# VNH2SP30_dual.net
KiCad netlist of a schematic drawn in EAGLE
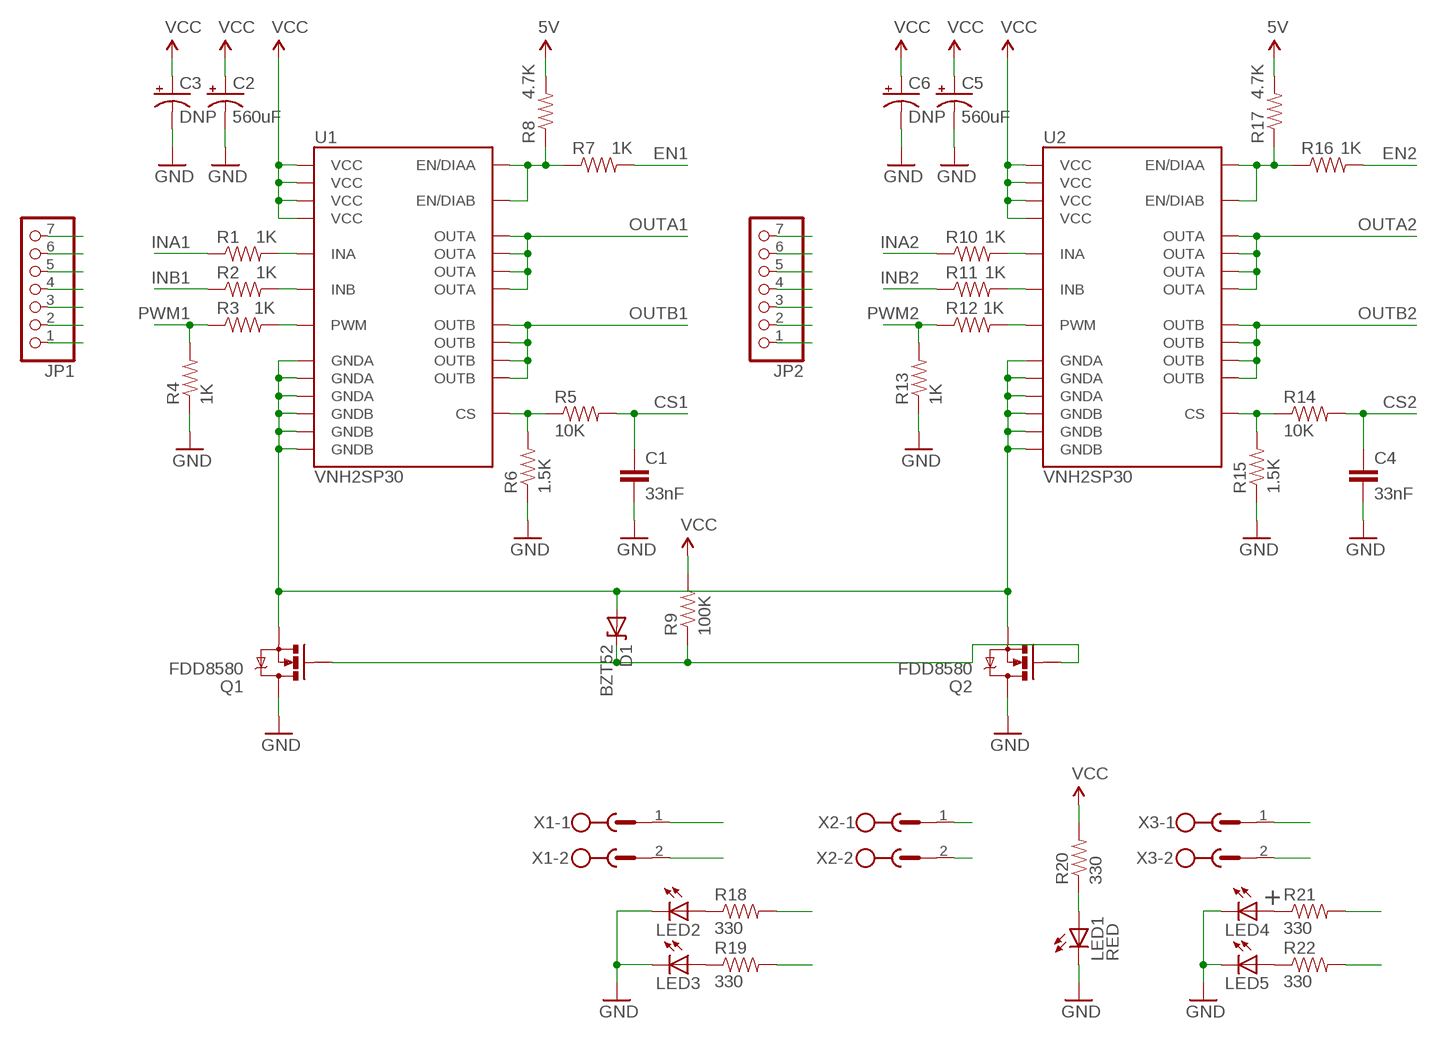
[diagram p0: schematic, sheet 1]

(export (version "E")
  (design (tool "Eeschema 10.0.6"))
  (components
    (comp (ref "C1")
      (value "33nF")
      (footprint "eagle-import:1206")
      (libsource (lib "eagle-import") (part "CAP1206"))
    )
    (comp (ref "C2")
      (value "560uF")
      (footprint "eagle-import:PANASONIC_G")
      (libsource (lib "eagle-import") (part "CAP_POLG"))
    )
    (comp (ref "C3")
      (value "DNP")
      (footprint "eagle-import:CPOL-RADIAL-1000UF-25V")
      (libsource (lib "eagle-import") (part "CAP_POLPTH4"))
    )
    (comp (ref "C4")
      (value "33nF")
      (footprint "eagle-import:1206")
      (libsource (lib "eagle-import") (part "CAP1206"))
    )
    (comp (ref "C5")
      (value "560uF")
      (footprint "eagle-import:PANASONIC_G")
      (libsource (lib "eagle-import") (part "CAP_POLG"))
    )
    (comp (ref "C6")
      (value "DNP")
      (footprint "eagle-import:CPOL-RADIAL-1000UF-25V")
      (libsource (lib "eagle-import") (part "CAP_POLPTH4"))
    )
    (comp (ref "D1")
      (value "BZT52")
      (footprint "eagle-import:SMB-DIODE")
      (libsource (lib "eagle-import") (part "DIODE-ZENERSMB"))
    )
    (comp (ref "JP1")
      (value "PINHD-1X7")
      (footprint "eagle-import:1X07")
      (libsource (lib "eagle-import") (part "PINHD-1X7"))
    )
    (comp (ref "JP2")
      (value "PINHD-1X7")
      (footprint "eagle-import:1X07")
      (libsource (lib "eagle-import") (part "PINHD-1X7"))
    )
    (comp (ref "LED1")
      (value "RED")
      (footprint "eagle-import:CHIPLED_1206")
      (libsource (lib "eagle-import") (part "LEDCHIPLED_1206"))
    )
    (comp (ref "LED2")
      (value "GREEN")
      (footprint "eagle-import:CHIPLED_1206")
      (libsource (lib "eagle-import") (part "LEDCHIPLED_1206"))
    )
    (comp (ref "LED3")
      (value "GREEN")
      (footprint "eagle-import:CHIPLED_1206")
      (libsource (lib "eagle-import") (part "LEDCHIPLED_1206"))
    )
    (comp (ref "LED4")
      (value "GREEN")
      (footprint "eagle-import:CHIPLED_1206")
      (libsource (lib "eagle-import") (part "LEDCHIPLED_1206"))
    )
    (comp (ref "LED5")
      (value "GREEN")
      (footprint "eagle-import:CHIPLED_1206")
      (libsource (lib "eagle-import") (part "LEDCHIPLED_1206"))
    )
    (comp (ref "Q1")
      (value "FDD8580")
      (footprint "eagle-import:DPAK")
      (libsource (lib "eagle-import") (part "MOSFET-NCHANNELFDD8580"))
    )
    (comp (ref "Q2")
      (value "FDD8580")
      (footprint "eagle-import:DPAK")
      (libsource (lib "eagle-import") (part "MOSFET-NCHANNELFDD8580"))
    )
    (comp (ref "R1")
      (value "1K")
      (footprint "eagle-import:1206")
      (libsource (lib "eagle-import") (part "RESISTOR1206"))
    )
    (comp (ref "R2")
      (value "1K")
      (footprint "eagle-import:1206")
      (libsource (lib "eagle-import") (part "RESISTOR1206"))
    )
    (comp (ref "R3")
      (value "1K")
      (footprint "eagle-import:1206")
      (libsource (lib "eagle-import") (part "RESISTOR1206"))
    )
    (comp (ref "R4")
      (value "1K")
      (footprint "eagle-import:1206")
      (libsource (lib "eagle-import") (part "RESISTOR1206"))
    )
    (comp (ref "R5")
      (value "10K")
      (footprint "eagle-import:1206")
      (libsource (lib "eagle-import") (part "RESISTOR1206"))
    )
    (comp (ref "R6")
      (value "1.5K")
      (footprint "eagle-import:1206")
      (libsource (lib "eagle-import") (part "RESISTOR1206"))
    )
    (comp (ref "R7")
      (value "1K")
      (footprint "eagle-import:1206")
      (libsource (lib "eagle-import") (part "RESISTOR1206"))
    )
    (comp (ref "R8")
      (value "4.7K")
      (footprint "eagle-import:1206")
      (libsource (lib "eagle-import") (part "RESISTOR1206"))
    )
    (comp (ref "R9")
      (value "100K")
      (footprint "eagle-import:1206")
      (libsource (lib "eagle-import") (part "RESISTOR1206"))
    )
    (comp (ref "R10")
      (value "1K")
      (footprint "eagle-import:1206")
      (libsource (lib "eagle-import") (part "RESISTOR1206"))
    )
    (comp (ref "R11")
      (value "1K")
      (footprint "eagle-import:1206")
      (libsource (lib "eagle-import") (part "RESISTOR1206"))
    )
    (comp (ref "R12")
      (value "1K")
      (footprint "eagle-import:1206")
      (libsource (lib "eagle-import") (part "RESISTOR1206"))
    )
    (comp (ref "R13")
      (value "1K")
      (footprint "eagle-import:1206")
      (libsource (lib "eagle-import") (part "RESISTOR1206"))
    )
    (comp (ref "R14")
      (value "10K")
      (footprint "eagle-import:1206")
      (libsource (lib "eagle-import") (part "RESISTOR1206"))
    )
    (comp (ref "R15")
      (value "1.5K")
      (footprint "eagle-import:1206")
      (libsource (lib "eagle-import") (part "RESISTOR1206"))
    )
    (comp (ref "R16")
      (value "1K")
      (footprint "eagle-import:1206")
      (libsource (lib "eagle-import") (part "RESISTOR1206"))
    )
    (comp (ref "R17")
      (value "4.7K")
      (footprint "eagle-import:1206")
      (libsource (lib "eagle-import") (part "RESISTOR1206"))
    )
    (comp (ref "R18")
      (value "330")
      (footprint "eagle-import:1206")
      (libsource (lib "eagle-import") (part "RESISTOR1206"))
    )
    (comp (ref "R19")
      (value "330")
      (footprint "eagle-import:1206")
      (libsource (lib "eagle-import") (part "RESISTOR1206"))
    )
    (comp (ref "R20")
      (value "330")
      (footprint "eagle-import:1206")
      (libsource (lib "eagle-import") (part "RESISTOR1206"))
    )
    (comp (ref "R21")
      (value "330")
      (footprint "eagle-import:1206")
      (libsource (lib "eagle-import") (part "RESISTOR1206"))
    )
    (comp (ref "R22")
      (value "330")
      (footprint "eagle-import:1206")
      (libsource (lib "eagle-import") (part "RESISTOR1206"))
    )
    (comp (ref "U1")
      (value "VNH2SP30")
      (footprint "eagle-import:VNH2SP30")
      (libsource (lib "eagle-import") (part "VNH2SP30"))
    )
    (comp (ref "U2")
      (value "VNH2SP30")
      (footprint "eagle-import:VNH2SP30")
      (libsource (lib "eagle-import") (part "VNH2SP30"))
    )
    (comp (ref "X1")
      (value "MSTBV2")
      (footprint "eagle-import:MSTBV2")
      (libsource (lib "eagle-import") (part "MSTBV2"))
    )
    (comp (ref "X2")
      (value "MSTBV2")
      (footprint "eagle-import:MSTBV2")
      (libsource (lib "eagle-import") (part "MSTBV2"))
    )
    (comp (ref "X3")
      (value "MSTBV2")
      (footprint "eagle-import:MSTBV2")
      (libsource (lib "eagle-import") (part "MSTBV2"))
    )
  )
  (nets
    (net (code "1") (name "/CS1") (class "Default")
      (node (ref "C1") (pin "1") (pinfunction "1_1") (pintype "passive"))
      (node (ref "JP1") (pin "2") (pinfunction "2_2") (pintype "passive"))
      (node (ref "R5") (pin "2") (pinfunction "2_2") (pintype "passive"))
    )
    (net (code "2") (name "/CS2") (class "Default")
      (node (ref "C4") (pin "1") (pinfunction "1_1") (pintype "passive"))
      (node (ref "JP2") (pin "2") (pinfunction "2_2") (pintype "passive"))
      (node (ref "R14") (pin "2") (pinfunction "2_2") (pintype "passive"))
    )
    (net (code "3") (name "/EN1") (class "Default")
      (node (ref "JP1") (pin "6") (pinfunction "6_6") (pintype "passive"))
      (node (ref "R7") (pin "2") (pinfunction "2_2") (pintype "passive"))
    )
    (net (code "4") (name "/EN2") (class "Default")
      (node (ref "JP2") (pin "6") (pinfunction "6_6") (pintype "passive"))
      (node (ref "R16") (pin "2") (pinfunction "2_2") (pintype "passive"))
    )
    (net (code "5") (name "/INA1") (class "Default")
      (node (ref "JP1") (pin "5") (pinfunction "5_5") (pintype "passive"))
      (node (ref "R1") (pin "1") (pinfunction "1_1") (pintype "passive"))
    )
    (net (code "6") (name "/INA2") (class "Default")
      (node (ref "JP2") (pin "5") (pinfunction "5_5") (pintype "passive"))
      (node (ref "R10") (pin "1") (pinfunction "1_1") (pintype "passive"))
    )
    (net (code "7") (name "/INB1") (class "Default")
      (node (ref "JP1") (pin "4") (pinfunction "4_4") (pintype "passive"))
      (node (ref "R2") (pin "1") (pinfunction "1_1") (pintype "passive"))
    )
    (net (code "8") (name "/INB2") (class "Default")
      (node (ref "JP2") (pin "4") (pinfunction "4_4") (pintype "passive"))
      (node (ref "R11") (pin "1") (pinfunction "1_1") (pintype "passive"))
    )
    (net (code "9") (name "/OUTA1") (class "Default")
      (node (ref "R18") (pin "2") (pinfunction "2_2") (pintype "passive"))
      (node (ref "U1") (pin "1") (pinfunction "OUTA_1") (pintype "bidirectional"))
      (node (ref "U1") (pin "25") (pinfunction "OUTA_25") (pintype "bidirectional"))
      (node (ref "U1") (pin "30") (pinfunction "OUTA_30") (pintype "bidirectional"))
      (node (ref "U1") (pin "SLUG3") (pinfunction "OUTA_SLUG3") (pintype "bidirectional"))
      (node (ref "X1") (pin "1") (pinfunction "SK_1") (pintype "passive"))
    )
    (net (code "10") (name "/OUTA2") (class "Default")
      (node (ref "R22") (pin "2") (pinfunction "2_2") (pintype "passive"))
      (node (ref "U2") (pin "1") (pinfunction "OUTA_1") (pintype "bidirectional"))
      (node (ref "U2") (pin "25") (pinfunction "OUTA_25") (pintype "bidirectional"))
      (node (ref "U2") (pin "30") (pinfunction "OUTA_30") (pintype "bidirectional"))
      (node (ref "U2") (pin "SLUG3") (pinfunction "OUTA_SLUG3") (pintype "bidirectional"))
      (node (ref "X3") (pin "1") (pinfunction "SK_1") (pintype "passive"))
    )
    (net (code "11") (name "/OUTB1") (class "Default")
      (node (ref "R19") (pin "2") (pinfunction "2_2") (pintype "passive"))
      (node (ref "U1") (pin "15") (pinfunction "OUTB_15") (pintype "bidirectional"))
      (node (ref "U1") (pin "16") (pinfunction "OUTB_16") (pintype "bidirectional"))
      (node (ref "U1") (pin "21") (pinfunction "OUTB_21") (pintype "bidirectional"))
      (node (ref "U1") (pin "SLUG2") (pinfunction "OUTB_SLUG2") (pintype "bidirectional"))
      (node (ref "X1") (pin "2") (pinfunction "SK_2") (pintype "passive"))
    )
    (net (code "12") (name "/OUTB2") (class "Default")
      (node (ref "R21") (pin "2") (pinfunction "2_2") (pintype "passive"))
      (node (ref "U2") (pin "15") (pinfunction "OUTB_15") (pintype "bidirectional"))
      (node (ref "U2") (pin "16") (pinfunction "OUTB_16") (pintype "bidirectional"))
      (node (ref "U2") (pin "21") (pinfunction "OUTB_21") (pintype "bidirectional"))
      (node (ref "U2") (pin "SLUG2") (pinfunction "OUTB_SLUG2") (pintype "bidirectional"))
      (node (ref "X3") (pin "2") (pinfunction "SK_2") (pintype "passive"))
    )
    (net (code "13") (name "/PWM1") (class "Default")
      (node (ref "JP1") (pin "3") (pinfunction "3_3") (pintype "passive"))
      (node (ref "R3") (pin "1") (pinfunction "1_1") (pintype "passive"))
      (node (ref "R4") (pin "2") (pinfunction "2_2") (pintype "passive"))
    )
    (net (code "14") (name "/PWM2") (class "Default")
      (node (ref "JP2") (pin "3") (pinfunction "3_3") (pintype "passive"))
      (node (ref "R12") (pin "1") (pinfunction "1_1") (pintype "passive"))
      (node (ref "R13") (pin "2") (pinfunction "2_2") (pintype "passive"))
    )
    (net (code "15") (name "5V") (class "Default")
      (node (ref "JP1") (pin "7") (pinfunction "7_7") (pintype "passive"))
      (node (ref "JP2") (pin "7") (pinfunction "7_7") (pintype "passive"))
      (node (ref "R17") (pin "2") (pinfunction "2_2") (pintype "passive"))
      (node (ref "R8") (pin "2") (pinfunction "2_2") (pintype "passive"))
    )
    (net (code "16") (name "GND") (class "Default")
      (node (ref "C1") (pin "2") (pinfunction "2_2") (pintype "passive"))
      (node (ref "C2") (pin "-") (pinfunction "-_-") (pintype "passive"))
      (node (ref "C3") (pin "2") (pinfunction "-_2") (pintype "passive"))
      (node (ref "C4") (pin "2") (pinfunction "2_2") (pintype "passive"))
      (node (ref "C5") (pin "-") (pinfunction "-_-") (pintype "passive"))
      (node (ref "C6") (pin "2") (pinfunction "-_2") (pintype "passive"))
      (node (ref "JP1") (pin "1") (pinfunction "1_1") (pintype "passive"))
      (node (ref "JP2") (pin "1") (pinfunction "1_1") (pintype "passive"))
      (node (ref "LED1") (pin "C") (pinfunction "C_C") (pintype "passive"))
      (node (ref "LED2") (pin "C") (pinfunction "C_C") (pintype "passive"))
      (node (ref "LED3") (pin "C") (pinfunction "C_C") (pintype "passive"))
      (node (ref "LED4") (pin "C") (pinfunction "C_C") (pintype "passive"))
      (node (ref "LED5") (pin "C") (pinfunction "C_C") (pintype "passive"))
      (node (ref "Q1") (pin "4") (pinfunction "D_4") (pintype "passive"))
      (node (ref "Q2") (pin "4") (pinfunction "D_4") (pintype "passive"))
      (node (ref "R13") (pin "1") (pinfunction "1_1") (pintype "passive"))
      (node (ref "R15") (pin "1") (pinfunction "1_1") (pintype "passive"))
      (node (ref "R4") (pin "1") (pinfunction "1_1") (pintype "passive"))
      (node (ref "R6") (pin "1") (pinfunction "1_1") (pintype "passive"))
      (node (ref "X2") (pin "1") (pinfunction "SK_1") (pintype "passive"))
    )
    (net (code "17") (name "Net-(LED1-PadA)") (class "Default")
      (node (ref "LED1") (pin "A") (pinfunction "A_A") (pintype "passive"))
      (node (ref "R20") (pin "1") (pinfunction "1_1") (pintype "passive"))
    )
    (net (code "18") (name "Net-(LED2-PadA)") (class "Default")
      (node (ref "LED2") (pin "A") (pinfunction "A_A") (pintype "passive"))
      (node (ref "R18") (pin "1") (pinfunction "1_1") (pintype "passive"))
    )
    (net (code "19") (name "Net-(LED3-PadA)") (class "Default")
      (node (ref "LED3") (pin "A") (pinfunction "A_A") (pintype "passive"))
      (node (ref "R19") (pin "1") (pinfunction "1_1") (pintype "passive"))
    )
    (net (code "20") (name "Net-(LED4-PadA)") (class "Default")
      (node (ref "LED4") (pin "A") (pinfunction "A_A") (pintype "passive"))
      (node (ref "R21") (pin "1") (pinfunction "1_1") (pintype "passive"))
    )
    (net (code "21") (name "Net-(LED5-PadA)") (class "Default")
      (node (ref "LED5") (pin "A") (pinfunction "A_A") (pintype "passive"))
      (node (ref "R22") (pin "1") (pinfunction "1_1") (pintype "passive"))
    )
    (net (code "22") (name "Net-(Q1-G)") (class "Default")
      (node (ref "D1") (pin "C") (pinfunction "C_C") (pintype "passive"))
      (node (ref "Q1") (pin "1") (pinfunction "G_1") (pintype "passive"))
      (node (ref "Q2") (pin "1") (pinfunction "G_1") (pintype "passive"))
      (node (ref "R9") (pin "1") (pinfunction "1_1") (pintype "passive"))
    )
    (net (code "23") (name "Net-(Q1-S)") (class "Default")
      (node (ref "D1") (pin "A") (pinfunction "A_A") (pintype "passive"))
      (node (ref "Q1") (pin "3") (pinfunction "S_3") (pintype "passive"))
      (node (ref "Q2") (pin "3") (pinfunction "S_3") (pintype "passive"))
      (node (ref "U1") (pin "18") (pinfunction "GNDB_18") (pintype "bidirectional"))
      (node (ref "U1") (pin "19") (pinfunction "GNDB_19") (pintype "bidirectional"))
      (node (ref "U1") (pin "20") (pinfunction "GNDB_20") (pintype "bidirectional"))
      (node (ref "U1") (pin "26") (pinfunction "GNDA_26") (pintype "bidirectional"))
      (node (ref "U1") (pin "27") (pinfunction "GNDA_27") (pintype "bidirectional"))
      (node (ref "U1") (pin "28") (pinfunction "GNDA_28") (pintype "bidirectional"))
      (node (ref "U2") (pin "18") (pinfunction "GNDB_18") (pintype "bidirectional"))
      (node (ref "U2") (pin "19") (pinfunction "GNDB_19") (pintype "bidirectional"))
      (node (ref "U2") (pin "20") (pinfunction "GNDB_20") (pintype "bidirectional"))
      (node (ref "U2") (pin "26") (pinfunction "GNDA_26") (pintype "bidirectional"))
      (node (ref "U2") (pin "27") (pinfunction "GNDA_27") (pintype "bidirectional"))
      (node (ref "U2") (pin "28") (pinfunction "GNDA_28") (pintype "bidirectional"))
    )
    (net (code "24") (name "Net-(U1-CS)") (class "Default")
      (node (ref "R5") (pin "1") (pinfunction "1_1") (pintype "passive"))
      (node (ref "R6") (pin "2") (pinfunction "2_2") (pintype "passive"))
      (node (ref "U1") (pin "9") (pinfunction "CS_9") (pintype "bidirectional"))
    )
    (net (code "25") (name "Net-(U1-EN{slash}DIAA)") (class "Default")
      (node (ref "R7") (pin "1") (pinfunction "1_1") (pintype "passive"))
      (node (ref "R8") (pin "1") (pinfunction "1_1") (pintype "passive"))
      (node (ref "U1") (pin "10") (pinfunction "EN/DIAB_10") (pintype "bidirectional"))
      (node (ref "U1") (pin "6") (pinfunction "EN/DIAA_6") (pintype "bidirectional"))
    )
    (net (code "26") (name "Net-(U1-INA)") (class "Default")
      (node (ref "R1") (pin "2") (pinfunction "2_2") (pintype "passive"))
      (node (ref "U1") (pin "5") (pinfunction "INA_5") (pintype "bidirectional"))
    )
    (net (code "27") (name "Net-(U1-INB)") (class "Default")
      (node (ref "R2") (pin "2") (pinfunction "2_2") (pintype "passive"))
      (node (ref "U1") (pin "11") (pinfunction "INB_11") (pintype "bidirectional"))
    )
    (net (code "28") (name "Net-(U1-PWM)") (class "Default")
      (node (ref "R3") (pin "2") (pinfunction "2_2") (pintype "passive"))
      (node (ref "U1") (pin "8") (pinfunction "PWM_8") (pintype "bidirectional"))
    )
    (net (code "29") (name "Net-(U2-CS)") (class "Default")
      (node (ref "R14") (pin "1") (pinfunction "1_1") (pintype "passive"))
      (node (ref "R15") (pin "2") (pinfunction "2_2") (pintype "passive"))
      (node (ref "U2") (pin "9") (pinfunction "CS_9") (pintype "bidirectional"))
    )
    (net (code "30") (name "Net-(U2-EN{slash}DIAA)") (class "Default")
      (node (ref "R16") (pin "1") (pinfunction "1_1") (pintype "passive"))
      (node (ref "R17") (pin "1") (pinfunction "1_1") (pintype "passive"))
      (node (ref "U2") (pin "10") (pinfunction "EN/DIAB_10") (pintype "bidirectional"))
      (node (ref "U2") (pin "6") (pinfunction "EN/DIAA_6") (pintype "bidirectional"))
    )
    (net (code "31") (name "Net-(U2-INA)") (class "Default")
      (node (ref "R10") (pin "2") (pinfunction "2_2") (pintype "passive"))
      (node (ref "U2") (pin "5") (pinfunction "INA_5") (pintype "bidirectional"))
    )
    (net (code "32") (name "Net-(U2-INB)") (class "Default")
      (node (ref "R11") (pin "2") (pinfunction "2_2") (pintype "passive"))
      (node (ref "U2") (pin "11") (pinfunction "INB_11") (pintype "bidirectional"))
    )
    (net (code "33") (name "Net-(U2-PWM)") (class "Default")
      (node (ref "R12") (pin "2") (pinfunction "2_2") (pintype "passive"))
      (node (ref "U2") (pin "8") (pinfunction "PWM_8") (pintype "bidirectional"))
    )
    (net (code "34") (name "VCC") (class "Default")
      (node (ref "C2") (pin "+") (pinfunction "+_+") (pintype "passive"))
      (node (ref "C3") (pin "1") (pinfunction "+_1") (pintype "passive"))
      (node (ref "C5") (pin "+") (pinfunction "+_+") (pintype "passive"))
      (node (ref "C6") (pin "1") (pinfunction "+_1") (pintype "passive"))
      (node (ref "R20") (pin "2") (pinfunction "2_2") (pintype "passive"))
      (node (ref "R9") (pin "2") (pinfunction "2_2") (pintype "passive"))
      (node (ref "U1") (pin "13") (pinfunction "VCC_13") (pintype "bidirectional"))
      (node (ref "U1") (pin "23") (pinfunction "VCC_23") (pintype "bidirectional"))
      (node (ref "U1") (pin "3") (pinfunction "VCC_3") (pintype "bidirectional"))
      (node (ref "U1") (pin "SLUG1") (pinfunction "VCC_SLUG1") (pintype "bidirectional"))
      (node (ref "U2") (pin "13") (pinfunction "VCC_13") (pintype "bidirectional"))
      (node (ref "U2") (pin "23") (pinfunction "VCC_23") (pintype "bidirectional"))
      (node (ref "U2") (pin "3") (pinfunction "VCC_3") (pintype "bidirectional"))
      (node (ref "U2") (pin "SLUG1") (pinfunction "VCC_SLUG1") (pintype "bidirectional"))
      (node (ref "X2") (pin "2") (pinfunction "SK_2") (pintype "passive"))
    )
  )
)
